# ProPrj_stm32_2025-12-13.net
KiCad netlist of a schematic drawn in EasyEDA Pro
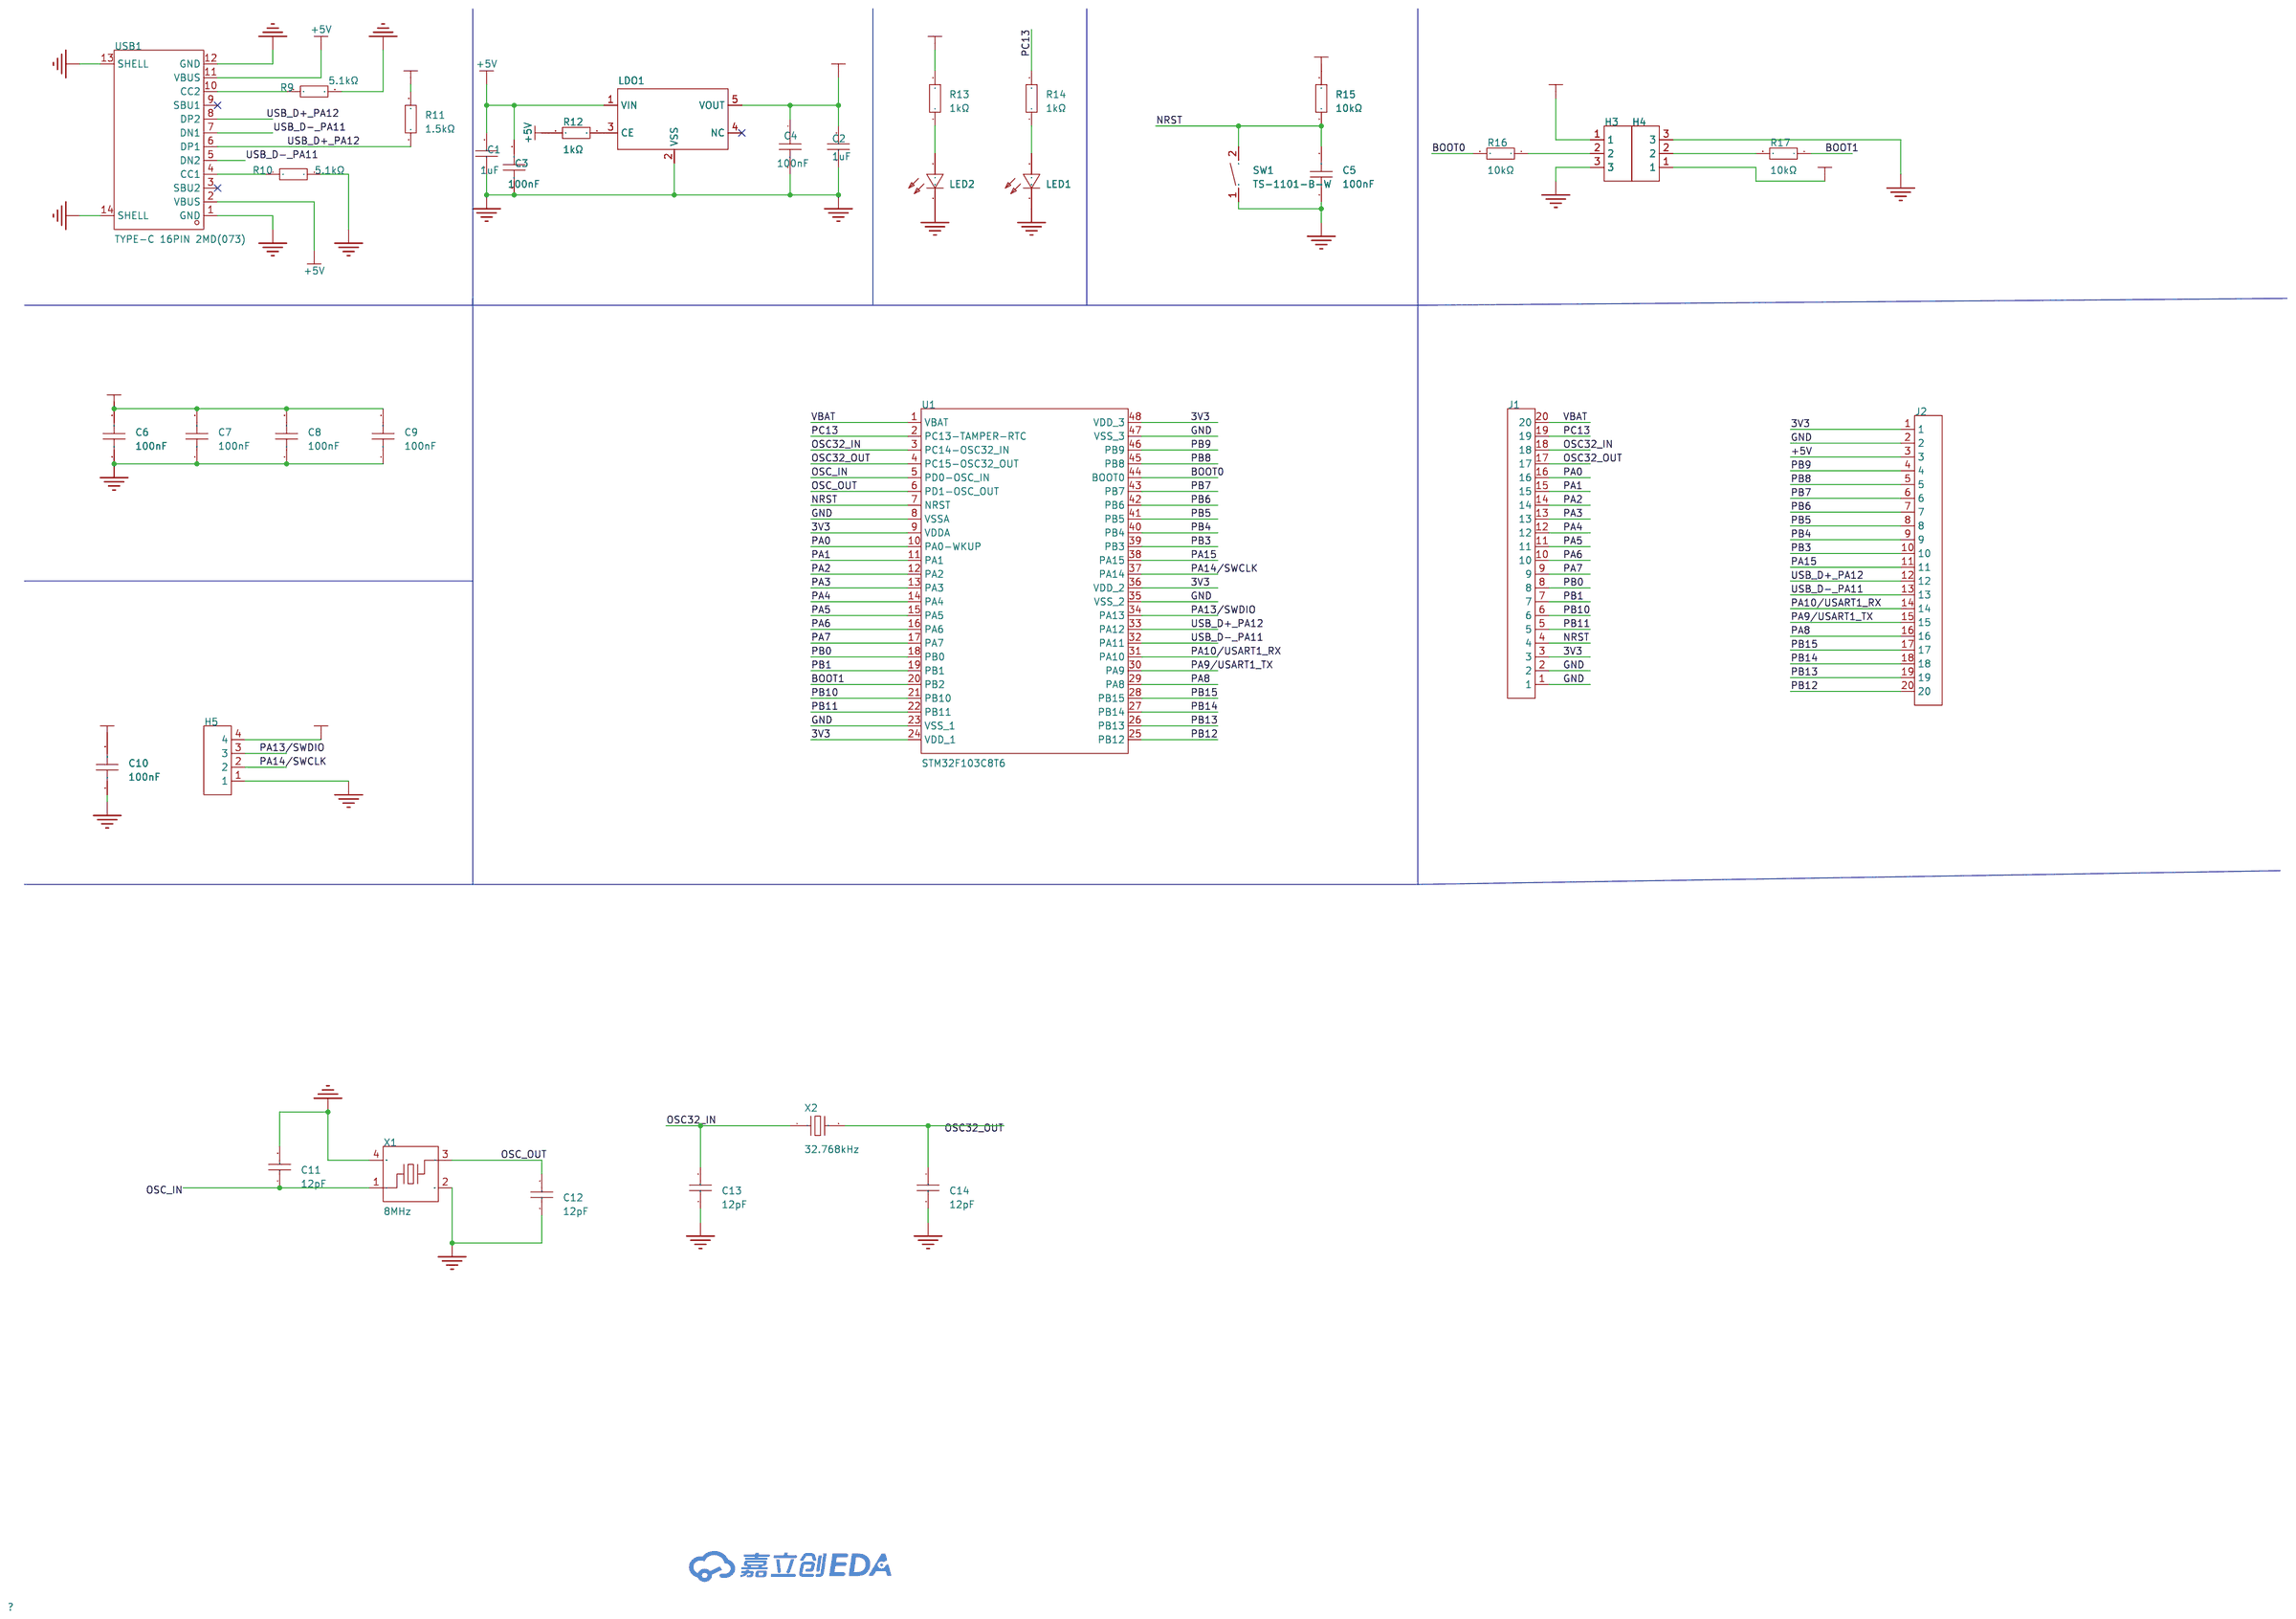
[diagram p0: schematic sheet]

(export (version "E")
  (design (tool "Eeschema 10.0.6"))
  (components
    (comp (ref "C1")
      (value "1uF")
      (footprint "easyedapro:C0402")
      (description "容值:1uF;精度:±10%;额定电压:10V;温度系数:X5R;")
      (fields
        (field (name "Manufacturer Part") "CL05A105KP5NNNC")
        (field (name "Manufacturer") "SAMSUNG(三星)")
      )
      (libsource (lib "easyedapro") (part "CL05A105KP5NNNC"))
    )
    (comp (ref "C2")
      (value "1uF")
      (footprint "easyedapro:C0402")
      (description "容值:1uF;精度:±10%;额定电压:10V;温度系数:X5R;")
      (fields
        (field (name "Manufacturer Part") "CL05A105KP5NNNC")
        (field (name "Manufacturer") "SAMSUNG(三星)")
      )
      (libsource (lib "easyedapro") (part "CL05A105KP5NNNC"))
    )
    (comp (ref "C3")
      (value "100nF")
      (footprint "easyedapro:C0402")
      (description "容值:100nF;精度:±10%;额定电压:50V;温度系数:X7R;")
      (fields
        (field (name "Manufacturer Part") "GRM155R71H104KE14D")
        (field (name "Manufacturer") "muRata(村田)")
      )
      (libsource (lib "easyedapro") (part "GRM155R71H104KE14D"))
    )
    (comp (ref "C4")
      (value "100nF")
      (footprint "easyedapro:C0402")
      (description "容值:100nF;精度:±10%;额定电压:50V;温度系数:X7R;")
      (fields
        (field (name "Manufacturer Part") "GRM155R71H104KE14D")
        (field (name "Manufacturer") "muRata(村田)")
      )
      (libsource (lib "easyedapro") (part "GRM155R71H104KE14D"))
    )
    (comp (ref "C5")
      (value "100nF")
      (footprint "easyedapro:C0402")
      (description "容值:100nF;精度:±10%;额定电压:50V;温度系数:X7R;")
      (fields
        (field (name "Manufacturer Part") "GRM155R71H104KE14D")
        (field (name "Manufacturer") "muRata(村田)")
      )
      (libsource (lib "easyedapro") (part "GRM155R71H104KE14D"))
    )
    (comp (ref "C6")
      (value "100nF")
      (footprint "easyedapro:C0402")
      (description "容值:100nF;精度:±10%;额定电压:50V;温度系数:X7R;")
      (fields
        (field (name "Manufacturer Part") "GRM155R71H104KE14D")
        (field (name "Manufacturer") "muRata(村田)")
      )
      (libsource (lib "easyedapro") (part "GRM155R71H104KE14D"))
    )
    (comp (ref "C7")
      (value "100nF")
      (footprint "easyedapro:C0402")
      (description "容值:100nF;精度:±10%;额定电压:50V;温度系数:X7R;")
      (fields
        (field (name "Manufacturer Part") "GRM155R71H104KE14D")
        (field (name "Manufacturer") "muRata(村田)")
      )
      (libsource (lib "easyedapro") (part "GRM155R71H104KE14D"))
    )
    (comp (ref "C8")
      (value "100nF")
      (footprint "easyedapro:C0402")
      (description "容值:100nF;精度:±10%;额定电压:50V;温度系数:X7R;")
      (fields
        (field (name "Manufacturer Part") "GRM155R71H104KE14D")
        (field (name "Manufacturer") "muRata(村田)")
      )
      (libsource (lib "easyedapro") (part "GRM155R71H104KE14D"))
    )
    (comp (ref "C9")
      (value "100nF")
      (footprint "easyedapro:C0402")
      (description "容值:100nF;精度:±10%;额定电压:50V;温度系数:X7R;")
      (fields
        (field (name "Manufacturer Part") "GRM155R71H104KE14D")
        (field (name "Manufacturer") "muRata(村田)")
      )
      (libsource (lib "easyedapro") (part "GRM155R71H104KE14D"))
    )
    (comp (ref "C10")
      (value "100nF")
      (footprint "easyedapro:C0402")
      (description "容值:100nF;精度:±10%;额定电压:50V;温度系数:X7R;")
      (fields
        (field (name "Manufacturer Part") "GRM155R71H104KE14D")
        (field (name "Manufacturer") "muRata(村田)")
      )
      (libsource (lib "easyedapro") (part "GRM155R71H104KE14D"))
    )
    (comp (ref "C11")
      (value "12pF")
      (footprint "easyedapro:C0402")
      (description "容值:12pF;精度:±5%;额定电压:50V;温度系数:C0G;")
      (fields (field (name "Manufacturer Part") "0402CG120J500NT") (field (name "Manufacturer") "FH(风华)"))
      (libsource (lib "easyedapro") (part "0402CG120J500NT"))
    )
    (comp (ref "C12")
      (value "12pF")
      (footprint "easyedapro:C0402")
      (description "容值:12pF;精度:±5%;额定电压:50V;温度系数:C0G;")
      (fields (field (name "Manufacturer Part") "0402CG120J500NT") (field (name "Manufacturer") "FH(风华)"))
      (libsource (lib "easyedapro") (part "0402CG120J500NT"))
    )
    (comp (ref "C13")
      (value "12pF")
      (footprint "easyedapro:C0402")
      (description "容值:12pF;精度:±5%;额定电压:50V;温度系数:C0G;")
      (fields (field (name "Manufacturer Part") "0402CG120J500NT") (field (name "Manufacturer") "FH(风华)"))
      (libsource (lib "easyedapro") (part "0402CG120J500NT"))
    )
    (comp (ref "C14")
      (value "12pF")
      (footprint "easyedapro:C0402")
      (description "容值:12pF;精度:±5%;额定电压:50V;温度系数:C0G;")
      (fields (field (name "Manufacturer Part") "0402CG120J500NT") (field (name "Manufacturer") "FH(风华)"))
      (libsource (lib "easyedapro") (part "0402CG120J500NT"))
    )
    (comp (ref "H3")
      (value "PZ254V-11-03P")
      (footprint "easyedapro:HDR-TH_3P-P2.54-V-M")
      (fields (field (name "Manufacturer") "XFCN(兴飞)"))
      (libsource (lib "easyedapro") (part "PZ254V-11-03P_C2937625"))
    )
    (comp (ref "H4")
      (value "PZ254V-11-03P")
      (footprint "easyedapro:HDR-TH_3P-P2.54-V-M")
      (fields (field (name "Manufacturer") "XFCN(兴飞)"))
      (libsource (lib "easyedapro") (part "PZ254V-11-03P_C2937625"))
    )
    (comp (ref "H5")
      (value "DZ254W-11-04-65")
      (footprint "easyedapro:HDR-TH_4P-P2.54-H-M-W10.3")
      (fields (field (name "Manufacturer") "DEALON(德艺隆)"))
      (libsource (lib "easyedapro") (part "DZ254W-11-04-65"))
    )
    (comp (ref "J1")
      (value "2.54-1*20P直针")
      (footprint "easyedapro:HDR-TH_20P-P2.54-V-M-1")
      (fields (field (name "Manufacturer") "BOOMELE(博穆精密)"))
      (libsource (lib "easyedapro") (part "Header-Male-2.54_1x20"))
    )
    (comp (ref "J2")
      (value "2.54-1*20P直针")
      (footprint "easyedapro:HDR-TH_20P-P2.54-V-M-1")
      (fields (field (name "Manufacturer") "BOOMELE(博穆精密)"))
      (libsource (lib "easyedapro") (part "Header-Male-2.54_1x20"))
    )
    (comp (ref "LDO1")
      (value "ME6211C33M5G-N")
      (footprint "easyedapro:SOT-23-5_L3.0-W1.7-P0.95-LS2.8-BL")
      (description "输出类型:固定;工作电压:6V;输出电压:3.3V;输出电流:500mA;电源纹波抑制比(PSRR):70dB@(1kHz);输出极性:正极;")
      (fields (field (name "Manufacturer") "MICRONE(南京微盟)"))
      (libsource (lib "easyedapro") (part "ME6211C33M5G-N"))
    )
    (comp (ref "LED1")
      (value "NCD0603R1")
      (footprint "easyedapro:LED0603-RD_RED")
      (fields (field (name "Manufacturer") "国星光电"))
      (libsource (lib "easyedapro") (part "FC-DA1608HRK-620D"))
    )
    (comp (ref "LED2")
      (value "NCD0603R1")
      (footprint "easyedapro:LED0603-RD_RED")
      (fields (field (name "Manufacturer") "国星光电"))
      (libsource (lib "easyedapro") (part "FC-DA1608HRK-620D"))
    )
    (comp (ref "R9")
      (value "5.1kΩ")
      (footprint "easyedapro:R0402")
      (description "电阻类型:厚膜电阻;阻值:5.1kΩ;精度:±1%;功率:62.5mW;工作电压:50V;温度系数:±100ppm/°C;")
      (fields
        (field (name "Manufacturer Part") "0402WGF5101TCE")
        (field (name "Manufacturer") "UNI-ROYAL(厚声)")
      )
      (libsource (lib "easyedapro") (part "0402WGF5101TCE"))
    )
    (comp (ref "R10")
      (value "5.1kΩ")
      (footprint "easyedapro:R0402")
      (description "电阻类型:厚膜电阻;阻值:5.1kΩ;精度:±1%;功率:62.5mW;工作电压:50V;温度系数:±100ppm/°C;")
      (fields
        (field (name "Manufacturer Part") "0402WGF5101TCE")
        (field (name "Manufacturer") "UNI-ROYAL(厚声)")
      )
      (libsource (lib "easyedapro") (part "0402WGF5101TCE"))
    )
    (comp (ref "R11")
      (value "1.5kΩ")
      (footprint "easyedapro:R0402")
      (description "电阻类型:厚膜电阻;阻值:1.5kΩ;精度:±1%;功率:62.5mW;最大工作电压:50V;温度系数:±100ppm/°C;")
      (fields
        (field (name "Manufacturer Part") "0402WGF1501TCE")
        (field (name "Manufacturer") "UNI-ROYAL(厚声)")
      )
      (libsource (lib "easyedapro") (part "0402WGF1501TCE"))
    )
    (comp (ref "R12")
      (value "1kΩ")
      (footprint "easyedapro:R0603")
      (description "电阻类型:厚膜电阻;阻值:1kΩ;精度:±1%;功率:100mW;工作电压:75V;温度系数:±100ppm/°C;")
      (fields
        (field (name "Manufacturer Part") "0603WAF1001T5E")
        (field (name "Manufacturer") "UNI-ROYAL(厚声)")
      )
      (libsource (lib "easyedapro") (part "0603WAF1001T5E"))
    )
    (comp (ref "R13")
      (value "1kΩ")
      (footprint "easyedapro:R0402")
      (description "电阻类型:厚膜电阻;阻值:1kΩ;精度:±1%;功率:62.5mW;工作电压:50V;温度系数:±100ppm/°C;")
      (fields
        (field (name "Manufacturer Part") "0402WGF1001TCE")
        (field (name "Manufacturer") "UNI-ROYAL(厚声)")
      )
      (libsource (lib "easyedapro") (part "0402WGF1001TCE"))
    )
    (comp (ref "R14")
      (value "1kΩ")
      (footprint "easyedapro:R0402")
      (description "电阻类型:厚膜电阻;阻值:1kΩ;精度:±1%;功率:62.5mW;工作电压:50V;温度系数:±100ppm/°C;")
      (fields
        (field (name "Manufacturer Part") "0402WGF1001TCE")
        (field (name "Manufacturer") "UNI-ROYAL(厚声)")
      )
      (libsource (lib "easyedapro") (part "0402WGF1001TCE"))
    )
    (comp (ref "R15")
      (value "10kΩ")
      (footprint "easyedapro:R0402")
      (description "电阻类型:厚膜电阻;阻值:10kΩ;精度:±1%;功率:62.5mW;工作电压:50V;温度系数:±100ppm/°C;")
      (fields (field (name "Manufacturer Part") "RC0402FR-0710KL") (field (name "Manufacturer") "YAGEO(国巨)"))
      (libsource (lib "easyedapro") (part "RC0402FR-0710KL"))
    )
    (comp (ref "R16")
      (value "10kΩ")
      (footprint "easyedapro:R0402")
      (description "电阻类型:厚膜电阻;阻值:10kΩ;精度:±1%;功率:62.5mW;工作电压:50V;温度系数:±100ppm/°C;")
      (fields (field (name "Manufacturer Part") "RC0402FR-0710KL") (field (name "Manufacturer") "YAGEO(国巨)"))
      (libsource (lib "easyedapro") (part "RC0402FR-0710KL"))
    )
    (comp (ref "R17")
      (value "10kΩ")
      (footprint "easyedapro:R0402")
      (description "电阻类型:厚膜电阻;阻值:10kΩ;精度:±1%;功率:62.5mW;工作电压:50V;温度系数:±100ppm/°C;")
      (fields (field (name "Manufacturer Part") "RC0402FR-0710KL") (field (name "Manufacturer") "YAGEO(国巨)"))
      (libsource (lib "easyedapro") (part "RC0402FR-0710KL"))
    )
    (comp (ref "SW1")
      (value "TS-1101-B-W")
      (footprint "easyedapro:KEY-SMD_2P-L6.0-W3.6-P7.4-LS8.0-L")
      (fields (field (name "Manufacturer") "XKB Connection(中国星坤)"))
      (libsource (lib "easyedapro") (part "TS-1101-B-W"))
    )
    (comp (ref "U1")
      (value "STM32F103C8T6")
      (footprint "easyedapro:LQFP-48_L7.0-W7.0-P0.50-LS9.0-BL")
      (description "CPU内核:ARM-M3;CPU最大主频:72MHz;应用领域:-;")
      (fields (field (name "Manufacturer") "ST(意法半导体)"))
      (libsource (lib "easyedapro") (part "STM32F103C8T6"))
    )
    (comp (ref "USB1")
      (value "TYPE-C 16PIN 2MD(073)")
      (footprint "easyedapro:USB-C-SMD_TYPE-C-6PIN-2MD-073")
      (description "连接器类型:Type-C;协议标准:-;公母:母;安装方式:卧贴;触点数量:16P;端口数量:1;额定电流 - 电源:3A;工作温度:-25°C~+85°C;")
      (fields (field (name "Manufacturer") "SHOU HAN(首韩)"))
      (libsource (lib "easyedapro") (part "TYPE-C 16PIN 2MD(073)"))
    )
    (comp (ref "X1")
      (value "8MHz")
      (footprint "easyedapro:CRYSTAL-SMD_4P-L3.2-W2.5-BL-1")
      (description "晶振类型:贴片晶振;频率:8MHz;常温频差:±10ppm;负载电容:12pF;频率稳定度:±20ppm;")
      (fields
        (field (name "Manufacturer Part") "XL2EL89COI-111YLC-8M")
        (field (name "Manufacturer") "YXC(扬兴晶振)")
      )
      (libsource (lib "easyedapro") (part "XL2EL89COI-111YLC-8M"))
    )
    (comp (ref "X2")
      (value "32.768kHz")
      (footprint "easyedapro:OSC-SMD_L3.2-W1.5")
      (description "晶振类型:贴片晶振;频率:32.768kHz;常温频差:±20ppm;负载电容:12.5pF;频率稳定度:±30ppm;")
      (fields (field (name "Manufacturer Part") "X321532768KGD2SI") (field (name "Manufacturer") "YXC(扬兴晶振)"))
      (libsource (lib "easyedapro") (part "X321532768KGD2SI"))
    )
  )
  (nets
    (net (code "1") (name "+5V") (class "Default")
      (node (ref "C1") (pin "2") (pinfunction "2_2") (pintype "input"))
      (node (ref "C3") (pin "1") (pinfunction "1_1") (pintype "unspecified"))
      (node (ref "J2") (pin "3") (pinfunction "3_3") (pintype "unspecified"))
      (node (ref "LDO1") (pin "1") (pinfunction "VIN_1") (pintype "unspecified"))
      (node (ref "R12") (pin "1") (pinfunction "1_1") (pintype "input"))
      (node (ref "USB1") (pin "11") (pinfunction "VBUS_11") (pintype "unspecified"))
      (node (ref "USB1") (pin "2") (pinfunction "VBUS_2") (pintype "unspecified"))
    )
    (net (code "2") (name "/BOOT0") (class "Default")
      (node (ref "R16") (pin "2") (pinfunction "2_2") (pintype "input"))
      (node (ref "U1") (pin "44") (pinfunction "BOOT0_44") (pintype "unspecified"))
    )
    (net (code "3") (name "/BOOT1") (class "Default")
      (node (ref "R17") (pin "1") (pinfunction "1_1") (pintype "input"))
      (node (ref "U1") (pin "20") (pinfunction "PB2_20") (pintype "unspecified"))
    )
    (net (code "4") (name "/NRST") (class "Default")
      (node (ref "C5") (pin "2") (pinfunction "2_2") (pintype "unspecified"))
      (node (ref "J1") (pin "4") (pinfunction "4_4") (pintype "unspecified"))
      (node (ref "R15") (pin "1") (pinfunction "1_1") (pintype "input"))
      (node (ref "SW1") (pin "2") (pinfunction "2_2") (pintype "unspecified"))
      (node (ref "U1") (pin "7") (pinfunction "NRST_7") (pintype "unspecified"))
    )
    (net (code "5") (name "/OSC32_IN") (class "Default")
      (node (ref "C13") (pin "2") (pinfunction "2_2") (pintype "input"))
      (node (ref "J1") (pin "18") (pinfunction "18_18") (pintype "unspecified"))
      (node (ref "U1") (pin "3") (pinfunction "PC14-OSC32_IN_3") (pintype "unspecified"))
      (node (ref "X2") (pin "1") (pinfunction "1_1") (pintype "input"))
    )
    (net (code "6") (name "/OSC32_OUT") (class "Default")
      (node (ref "C14") (pin "2") (pinfunction "2_2") (pintype "input"))
      (node (ref "J1") (pin "17") (pinfunction "17_17") (pintype "unspecified"))
      (node (ref "U1") (pin "4") (pinfunction "PC15-OSC32_OUT_4") (pintype "unspecified"))
      (node (ref "X2") (pin "2") (pinfunction "2_2") (pintype "input"))
    )
    (net (code "7") (name "/OSC_IN") (class "Default")
      (node (ref "C11") (pin "1") (pinfunction "1_1") (pintype "input"))
      (node (ref "U1") (pin "5") (pinfunction "PD0-OSC_IN_5") (pintype "unspecified"))
      (node (ref "X1") (pin "1") (pinfunction "1_1") (pintype "input"))
    )
    (net (code "8") (name "/OSC_OUT") (class "Default")
      (node (ref "C12") (pin "2") (pinfunction "2_2") (pintype "input"))
      (node (ref "U1") (pin "6") (pinfunction "PD1-OSC_OUT_6") (pintype "unspecified"))
      (node (ref "X1") (pin "3") (pinfunction "3_3") (pintype "input"))
    )
    (net (code "9") (name "/PA0") (class "Default")
      (node (ref "J1") (pin "16") (pinfunction "16_16") (pintype "unspecified"))
      (node (ref "U1") (pin "10") (pinfunction "PA0-WKUP_10") (pintype "unspecified"))
    )
    (net (code "10") (name "/PA1") (class "Default")
      (node (ref "J1") (pin "15") (pinfunction "15_15") (pintype "unspecified"))
      (node (ref "U1") (pin "11") (pinfunction "PA1_11") (pintype "unspecified"))
    )
    (net (code "11") (name "/PA2") (class "Default")
      (node (ref "J1") (pin "14") (pinfunction "14_14") (pintype "unspecified"))
      (node (ref "U1") (pin "12") (pinfunction "PA2_12") (pintype "unspecified"))
    )
    (net (code "12") (name "/PA3") (class "Default")
      (node (ref "J1") (pin "13") (pinfunction "13_13") (pintype "unspecified"))
      (node (ref "U1") (pin "13") (pinfunction "PA3_13") (pintype "unspecified"))
    )
    (net (code "13") (name "/PA4") (class "Default")
      (node (ref "J1") (pin "12") (pinfunction "12_12") (pintype "unspecified"))
      (node (ref "U1") (pin "14") (pinfunction "PA4_14") (pintype "unspecified"))
    )
    (net (code "14") (name "/PA5") (class "Default")
      (node (ref "J1") (pin "11") (pinfunction "11_11") (pintype "unspecified"))
      (node (ref "U1") (pin "15") (pinfunction "PA5_15") (pintype "unspecified"))
    )
    (net (code "15") (name "/PA6") (class "Default")
      (node (ref "J1") (pin "10") (pinfunction "10_10") (pintype "unspecified"))
      (node (ref "U1") (pin "16") (pinfunction "PA6_16") (pintype "unspecified"))
    )
    (net (code "16") (name "/PA7") (class "Default")
      (node (ref "J1") (pin "9") (pinfunction "9_9") (pintype "unspecified"))
      (node (ref "U1") (pin "17") (pinfunction "PA7_17") (pintype "unspecified"))
    )
    (net (code "17") (name "/PA8") (class "Default")
      (node (ref "J2") (pin "16") (pinfunction "16_16") (pintype "unspecified"))
      (node (ref "U1") (pin "29") (pinfunction "PA8_29") (pintype "unspecified"))
    )
    (net (code "18") (name "/PA9{slash}USART1_TX") (class "Default")
      (node (ref "J2") (pin "15") (pinfunction "15_15") (pintype "unspecified"))
      (node (ref "U1") (pin "30") (pinfunction "PA9_30") (pintype "unspecified"))
    )
    (net (code "19") (name "/PA10{slash}USART1_RX") (class "Default")
      (node (ref "J2") (pin "14") (pinfunction "14_14") (pintype "unspecified"))
      (node (ref "U1") (pin "31") (pinfunction "PA10_31") (pintype "unspecified"))
    )
    (net (code "20") (name "/PA13{slash}SWDIO") (class "Default")
      (node (ref "H5") (pin "3") (pinfunction "3_3") (pintype "unspecified"))
      (node (ref "U1") (pin "34") (pinfunction "PA13_34") (pintype "unspecified"))
    )
    (net (code "21") (name "/PA14{slash}SWCLK") (class "Default")
      (node (ref "H5") (pin "2") (pinfunction "2_2") (pintype "unspecified"))
      (node (ref "U1") (pin "37") (pinfunction "PA14_37") (pintype "unspecified"))
    )
    (net (code "22") (name "/PA15") (class "Default")
      (node (ref "J2") (pin "11") (pinfunction "11_11") (pintype "unspecified"))
      (node (ref "U1") (pin "38") (pinfunction "PA15_38") (pintype "unspecified"))
    )
    (net (code "23") (name "/PB0") (class "Default")
      (node (ref "J1") (pin "8") (pinfunction "8_8") (pintype "unspecified"))
      (node (ref "U1") (pin "18") (pinfunction "PB0_18") (pintype "unspecified"))
    )
    (net (code "24") (name "/PB1") (class "Default")
      (node (ref "J1") (pin "7") (pinfunction "7_7") (pintype "unspecified"))
      (node (ref "U1") (pin "19") (pinfunction "PB1_19") (pintype "unspecified"))
    )
    (net (code "25") (name "/PB3") (class "Default")
      (node (ref "J2") (pin "10") (pinfunction "10_10") (pintype "unspecified"))
      (node (ref "U1") (pin "39") (pinfunction "PB3_39") (pintype "unspecified"))
    )
    (net (code "26") (name "/PB4") (class "Default")
      (node (ref "J2") (pin "9") (pinfunction "9_9") (pintype "unspecified"))
      (node (ref "U1") (pin "40") (pinfunction "PB4_40") (pintype "unspecified"))
    )
    (net (code "27") (name "/PB5") (class "Default")
      (node (ref "J2") (pin "8") (pinfunction "8_8") (pintype "unspecified"))
      (node (ref "U1") (pin "41") (pinfunction "PB5_41") (pintype "unspecified"))
    )
    (net (code "28") (name "/PB6") (class "Default")
      (node (ref "J2") (pin "7") (pinfunction "7_7") (pintype "unspecified"))
      (node (ref "U1") (pin "42") (pinfunction "PB6_42") (pintype "unspecified"))
    )
    (net (code "29") (name "/PB7") (class "Default")
      (node (ref "J2") (pin "6") (pinfunction "6_6") (pintype "unspecified"))
      (node (ref "U1") (pin "43") (pinfunction "PB7_43") (pintype "unspecified"))
    )
    (net (code "30") (name "/PB8") (class "Default")
      (node (ref "J2") (pin "5") (pinfunction "5_5") (pintype "unspecified"))
      (node (ref "U1") (pin "45") (pinfunction "PB8_45") (pintype "unspecified"))
    )
    (net (code "31") (name "/PB9") (class "Default")
      (node (ref "J2") (pin "4") (pinfunction "4_4") (pintype "unspecified"))
      (node (ref "U1") (pin "46") (pinfunction "PB9_46") (pintype "unspecified"))
    )
    (net (code "32") (name "/PB10") (class "Default")
      (node (ref "J1") (pin "6") (pinfunction "6_6") (pintype "unspecified"))
      (node (ref "U1") (pin "21") (pinfunction "PB10_21") (pintype "unspecified"))
    )
    (net (code "33") (name "/PB11") (class "Default")
      (node (ref "J1") (pin "5") (pinfunction "5_5") (pintype "unspecified"))
      (node (ref "U1") (pin "22") (pinfunction "PB11_22") (pintype "unspecified"))
    )
    (net (code "34") (name "/PB12") (class "Default")
      (node (ref "J2") (pin "20") (pinfunction "20_20") (pintype "unspecified"))
      (node (ref "U1") (pin "25") (pinfunction "PB12_25") (pintype "unspecified"))
    )
    (net (code "35") (name "/PB13") (class "Default")
      (node (ref "J2") (pin "19") (pinfunction "19_19") (pintype "unspecified"))
      (node (ref "U1") (pin "26") (pinfunction "PB13_26") (pintype "unspecified"))
    )
    (net (code "36") (name "/PB14") (class "Default")
      (node (ref "J2") (pin "18") (pinfunction "18_18") (pintype "unspecified"))
      (node (ref "U1") (pin "27") (pinfunction "PB14_27") (pintype "unspecified"))
    )
    (net (code "37") (name "/PB15") (class "Default")
      (node (ref "J2") (pin "17") (pinfunction "17_17") (pintype "unspecified"))
      (node (ref "U1") (pin "28") (pinfunction "PB15_28") (pintype "unspecified"))
    )
    (net (code "38") (name "/PC13") (class "Default")
      (node (ref "J1") (pin "19") (pinfunction "19_19") (pintype "unspecified"))
      (node (ref "R14") (pin "2") (pinfunction "2_2") (pintype "input"))
      (node (ref "U1") (pin "2") (pinfunction "PC13-TAMPER-RTC_2") (pintype "unspecified"))
    )
    (net (code "39") (name "/USB_D+_PA12") (class "Default")
      (node (ref "J2") (pin "12") (pinfunction "12_12") (pintype "unspecified"))
      (node (ref "R11") (pin "1") (pinfunction "1_1") (pintype "input"))
      (node (ref "U1") (pin "33") (pinfunction "PA12_33") (pintype "unspecified"))
      (node (ref "USB1") (pin "6") (pinfunction "DP1_6") (pintype "unspecified"))
      (node (ref "USB1") (pin "8") (pinfunction "DP2_8") (pintype "unspecified"))
    )
    (net (code "40") (name "/USB_D-_PA11") (class "Default")
      (node (ref "J2") (pin "13") (pinfunction "13_13") (pintype "unspecified"))
      (node (ref "U1") (pin "32") (pinfunction "PA11_32") (pintype "unspecified"))
      (node (ref "USB1") (pin "5") (pinfunction "DN2_5") (pintype "unspecified"))
      (node (ref "USB1") (pin "7") (pinfunction "DN1_7") (pintype "unspecified"))
    )
    (net (code "41") (name "/VBAT") (class "Default")
      (node (ref "J1") (pin "20") (pinfunction "20_20") (pintype "unspecified"))
      (node (ref "U1") (pin "1") (pinfunction "VBAT_1") (pintype "unspecified"))
    )
    (net (code "42") (name "3.3V") (class "Default")
      (node (ref "C2") (pin "2") (pinfunction "2_2") (pintype "input"))
      (node (ref "C4") (pin "1") (pinfunction "1_1") (pintype "unspecified"))
      (node (ref "LDO1") (pin "5") (pinfunction "VOUT_5") (pintype "unspecified"))
      (node (ref "R11") (pin "2") (pinfunction "2_2") (pintype "input"))
    )
    (net (code "43") (name "3V3") (class "Default")
      (node (ref "C10") (pin "2") (pinfunction "2_2") (pintype "unspecified"))
      (node (ref "C6") (pin "2") (pinfunction "2_2") (pintype "unspecified"))
      (node (ref "C7") (pin "2") (pinfunction "2_2") (pintype "unspecified"))
      (node (ref "C8") (pin "2") (pinfunction "2_2") (pintype "unspecified"))
      (node (ref "C9") (pin "2") (pinfunction "2_2") (pintype "unspecified"))
      (node (ref "H3") (pin "1") (pinfunction "1_1") (pintype "unspecified"))
      (node (ref "H4") (pin "1") (pinfunction "1_1") (pintype "unspecified"))
      (node (ref "H5") (pin "4") (pinfunction "4_4") (pintype "unspecified"))
      (node (ref "J1") (pin "3") (pinfunction "3_3") (pintype "unspecified"))
      (node (ref "J2") (pin "1") (pinfunction "1_1") (pintype "unspecified"))
      (node (ref "R13") (pin "2") (pinfunction "2_2") (pintype "input"))
      (node (ref "R15") (pin "2") (pinfunction "2_2") (pintype "input"))
      (node (ref "U1") (pin "24") (pinfunction "VDD_1_24") (pintype "unspecified"))
      (node (ref "U1") (pin "36") (pinfunction "VDD_2_36") (pintype "unspecified"))
      (node (ref "U1") (pin "48") (pinfunction "VDD_3_48") (pintype "unspecified"))
      (node (ref "U1") (pin "9") (pinfunction "VDDA_9") (pintype "unspecified"))
    )
    (net (code "44") (name "GND") (class "Default")
      (node (ref "C1") (pin "1") (pinfunction "1_1") (pintype "input"))
      (node (ref "C10") (pin "1") (pinfunction "1_1") (pintype "unspecified"))
      (node (ref "C11") (pin "2") (pinfunction "2_2") (pintype "input"))
      (node (ref "C12") (pin "1") (pinfunction "1_1") (pintype "input"))
      (node (ref "C13") (pin "1") (pinfunction "1_1") (pintype "input"))
      (node (ref "C14") (pin "1") (pinfunction "1_1") (pintype "input"))
      (node (ref "C2") (pin "1") (pinfunction "1_1") (pintype "input"))
      (node (ref "C3") (pin "2") (pinfunction "2_2") (pintype "unspecified"))
      (node (ref "C4") (pin "2") (pinfunction "2_2") (pintype "unspecified"))
      (node (ref "C5") (pin "1") (pinfunction "1_1") (pintype "unspecified"))
      (node (ref "C6") (pin "1") (pinfunction "1_1") (pintype "unspecified"))
      (node (ref "C7") (pin "1") (pinfunction "1_1") (pintype "unspecified"))
      (node (ref "C8") (pin "1") (pinfunction "1_1") (pintype "unspecified"))
      (node (ref "C9") (pin "1") (pinfunction "1_1") (pintype "unspecified"))
      (node (ref "H3") (pin "3") (pinfunction "3_3") (pintype "unspecified"))
      (node (ref "H4") (pin "3") (pinfunction "3_3") (pintype "unspecified"))
      (node (ref "H5") (pin "1") (pinfunction "1_1") (pintype "unspecified"))
      (node (ref "J1") (pin "1") (pinfunction "1_1") (pintype "unspecified"))
      (node (ref "J1") (pin "2") (pinfunction "2_2") (pintype "unspecified"))
      (node (ref "J2") (pin "2") (pinfunction "2_2") (pintype "unspecified"))
      (node (ref "LDO1") (pin "2") (pinfunction "VSS_2") (pintype "unspecified"))
      (node (ref "LED1") (pin "1") (pinfunction "K_1") (pintype "input"))
      (node (ref "LED2") (pin "1") (pinfunction "K_1") (pintype "input"))
      (node (ref "R10") (pin "2") (pinfunction "2_2") (pintype "input"))
      (node (ref "R9") (pin "2") (pinfunction "2_2") (pintype "input"))
      (node (ref "SW1") (pin "1") (pinfunction "1_1") (pintype "unspecified"))
      (node (ref "U1") (pin "23") (pinfunction "VSS_1_23") (pintype "unspecified"))
      (node (ref "U1") (pin "35") (pinfunction "VSS_2_35") (pintype "unspecified"))
      (node (ref "U1") (pin "47") (pinfunction "VSS_3_47") (pintype "unspecified"))
      (node (ref "U1") (pin "8") (pinfunction "VSSA_8") (pintype "unspecified"))
      (node (ref "USB1") (pin "1") (pinfunction "GND_1") (pintype "unspecified"))
      (node (ref "USB1") (pin "12") (pinfunction "GND_12") (pintype "unspecified"))
      (node (ref "USB1") (pin "13") (pinfunction "SHELL_13") (pintype "unspecified"))
      (node (ref "USB1") (pin "14") (pinfunction "SHELL_14") (pintype "unspecified"))
      (node (ref "X1") (pin "2") (pinfunction "GND_2") (pintype "input"))
      (node (ref "X1") (pin "4") (pinfunction "GND_4") (pintype "input"))
    )
    (net (code "45") (name "Net-(H3-Pad2)") (class "Default")
      (node (ref "H3") (pin "2") (pinfunction "2_2") (pintype "unspecified"))
      (node (ref "R16") (pin "1") (pinfunction "1_1") (pintype "input"))
    )
    (net (code "46") (name "Net-(H4-Pad2)") (class "Default")
      (node (ref "H4") (pin "2") (pinfunction "2_2") (pintype "unspecified"))
      (node (ref "R17") (pin "2") (pinfunction "2_2") (pintype "input"))
    )
    (net (code "47") (name "Net-(LDO1-CE)") (class "Default")
      (node (ref "LDO1") (pin "3") (pinfunction "CE_3") (pintype "unspecified"))
      (node (ref "R12") (pin "2") (pinfunction "2_2") (pintype "input"))
    )
    (net (code "48") (name "Net-(LED1-A)") (class "Default")
      (node (ref "LED1") (pin "2") (pinfunction "A_2") (pintype "input"))
      (node (ref "R14") (pin "1") (pinfunction "1_1") (pintype "input"))
    )
    (net (code "49") (name "Net-(LED2-A)") (class "Default")
      (node (ref "LED2") (pin "2") (pinfunction "A_2") (pintype "input"))
      (node (ref "R13") (pin "1") (pinfunction "1_1") (pintype "input"))
    )
    (net (code "50") (name "Net-(USB1-CC1)") (class "Default")
      (node (ref "R10") (pin "1") (pinfunction "1_1") (pintype "input"))
      (node (ref "USB1") (pin "4") (pinfunction "CC1_4") (pintype "unspecified"))
    )
    (net (code "51") (name "Net-(USB1-CC2)") (class "Default")
      (node (ref "R9") (pin "1") (pinfunction "1_1") (pintype "input"))
      (node (ref "USB1") (pin "10") (pinfunction "CC2_10") (pintype "unspecified"))
    )
    (net (code "52") (name "unconnected-(LDO1-NC-Pad4)") (class "Default")
      (node (ref "LDO1") (pin "4") (pinfunction "NC_4") (pintype "unspecified+no_connect"))
    )
    (net (code "53") (name "unconnected-(USB1-SBU1-Pad9)") (class "Default")
      (node (ref "USB1") (pin "9") (pinfunction "SBU1_9") (pintype "unspecified+no_connect"))
    )
    (net (code "54") (name "unconnected-(USB1-SBU2-Pad3)") (class "Default")
      (node (ref "USB1") (pin "3") (pinfunction "SBU2_3") (pintype "unspecified+no_connect"))
    )
  )
)
